# axiom_beta_power_adapter.net
KiCad netlist of a schematic drawn in EAGLE
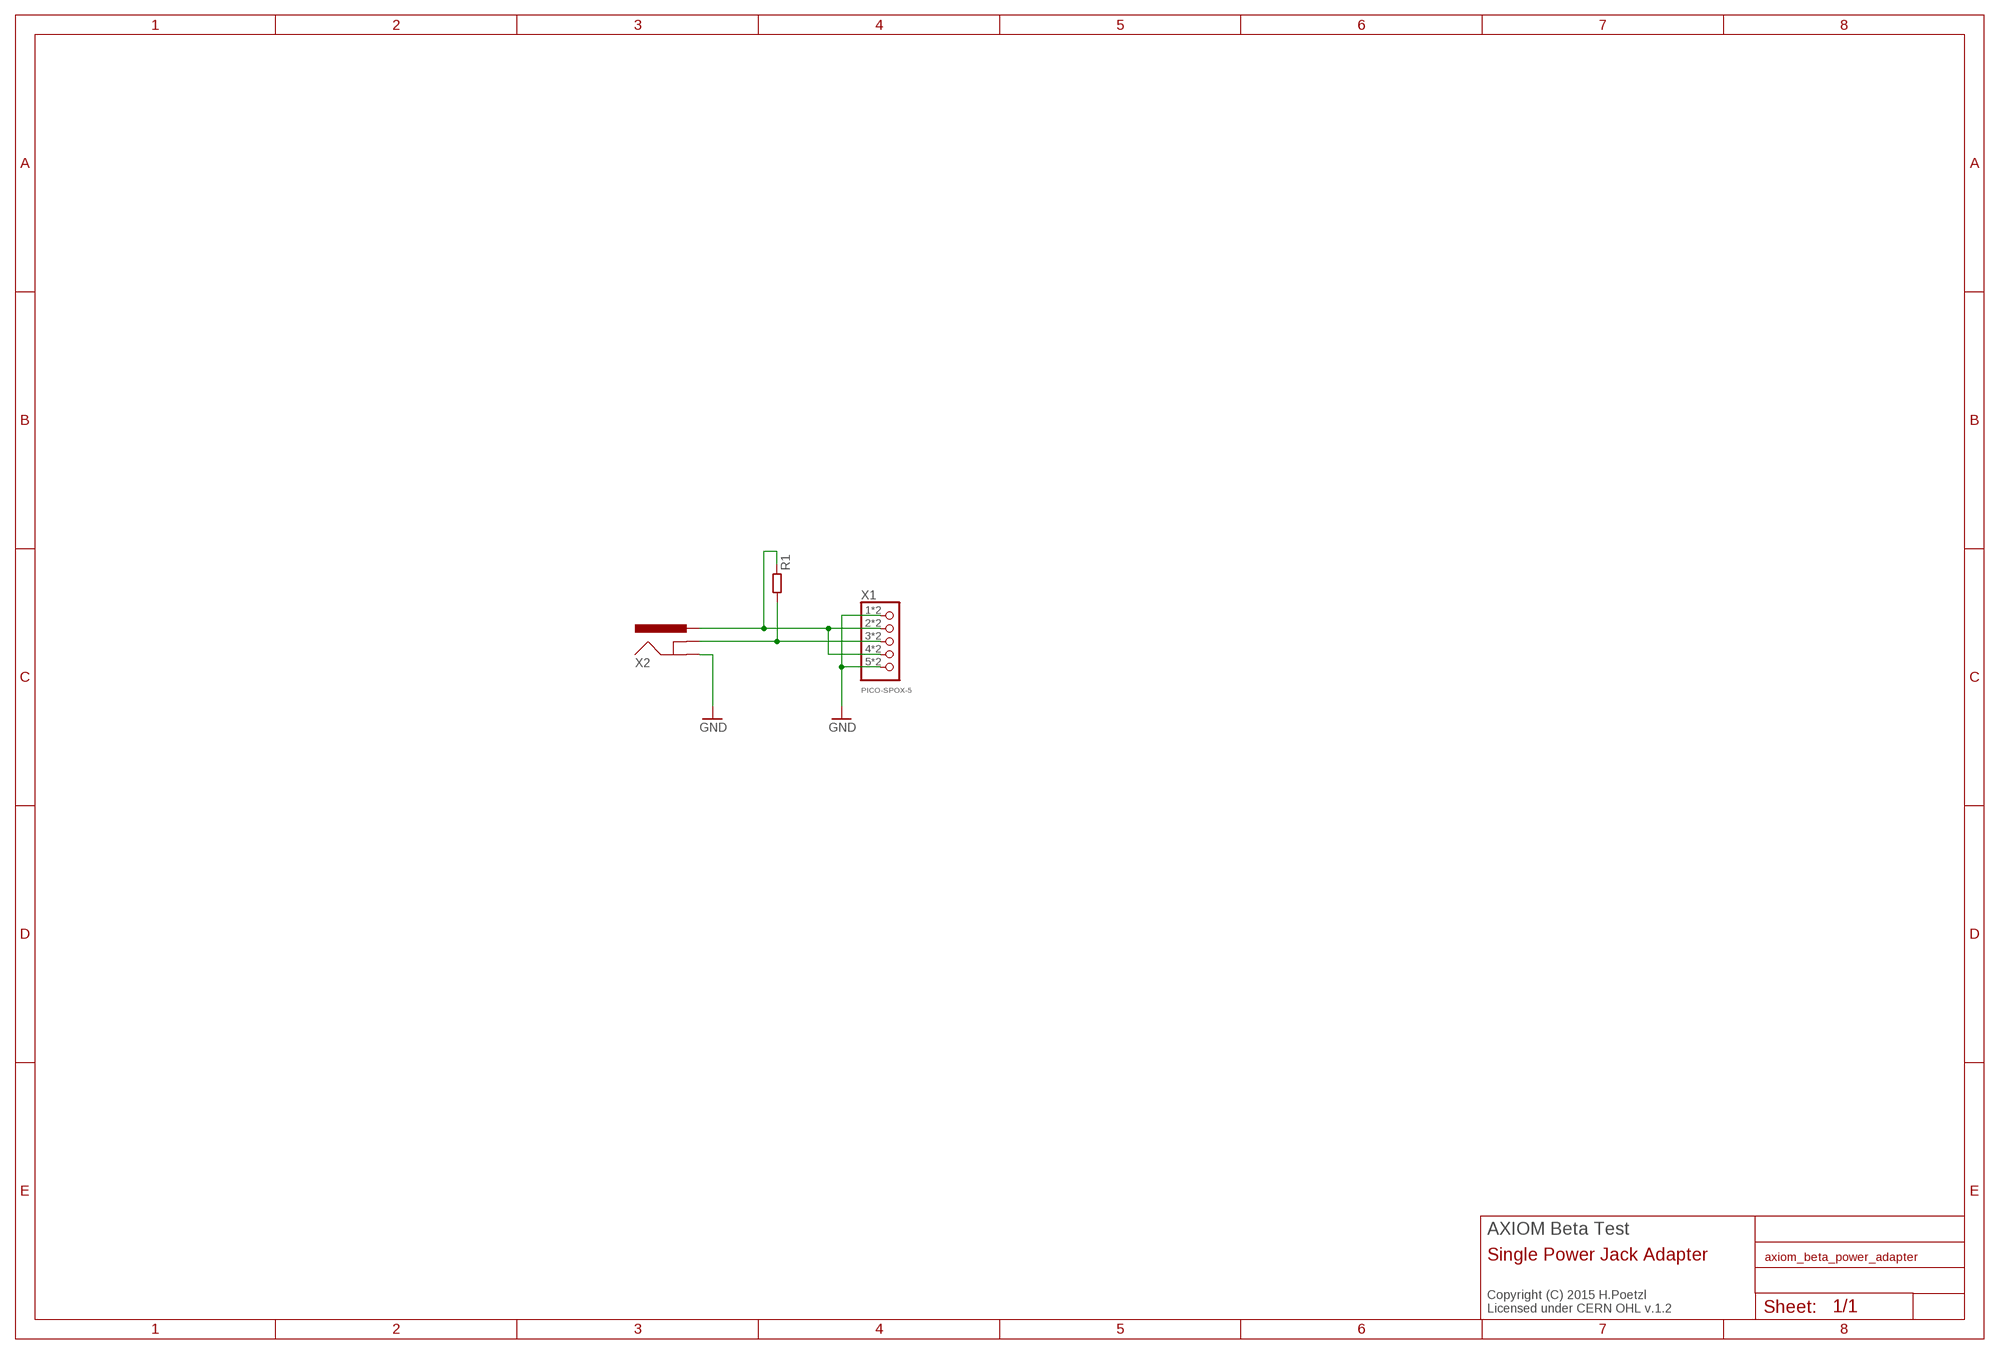
[diagram p0: schematic, sheet 1]

(export (version "E")
  (design (tool "Eeschema 10.0.6"))
  (components
    (comp (ref "R1")
      (value "R0402-B")
      (footprint "eagle-import:0402-B")
      (libsource (lib "eagle-import") (part "R0402-B"))
    )
    (comp (ref "X1")
      (value "PICO-SPOX-5")
      (footprint "eagle-import:PICO-SPOX-5")
      (libsource (lib "eagle-import") (part "PICO-SPOX-5"))
    )
    (comp (ref "X2")
      (value "POWER_JACKPTH_N")
      (footprint "eagle-import:POWER_JACK_PTH_NARROW")
      (libsource (lib "eagle-import") (part "POWER_JACKPTH_N"))
    )
  )
  (nets
    (net (code "1") (name "GND") (class "Default")
      (node (ref "X1") (pin "1") (pinfunction "1_1") (pintype "passive"))
      (node (ref "X1") (pin "1A") (pinfunction "1_1A") (pintype "passive"))
      (node (ref "X1") (pin "5") (pinfunction "5_5") (pintype "passive"))
      (node (ref "X1") (pin "5A") (pinfunction "5_5A") (pintype "passive"))
      (node (ref "X2") (pin "GND") (pinfunction "GND_GND") (pintype "bidirectional"))
    )
    (net (code "2") (name "Net-(R1-Pad1)") (class "Default")
      (node (ref "R1") (pin "1") (pinfunction "1_1") (pintype "passive"))
      (node (ref "X1") (pin "2") (pinfunction "2_2") (pintype "passive"))
      (node (ref "X1") (pin "2A") (pinfunction "2_2A") (pintype "passive"))
      (node (ref "X1") (pin "4") (pinfunction "4_4") (pintype "passive"))
      (node (ref "X1") (pin "4A") (pinfunction "4_4A") (pintype "passive"))
      (node (ref "X2") (pin "PWR") (pinfunction "PWR_PWR") (pintype "bidirectional"))
    )
    (net (code "3") (name "Net-(X2-GNDBREAK)") (class "Default")
      (node (ref "R1") (pin "2") (pinfunction "2_2") (pintype "passive"))
      (node (ref "X1") (pin "3") (pinfunction "3_3") (pintype "passive"))
      (node (ref "X1") (pin "3A") (pinfunction "3_3A") (pintype "passive"))
      (node (ref "X2") (pin "SHUNT") (pinfunction "GNDBREAK_SHUNT") (pintype "bidirectional"))
    )
  )
)
